# carte_ninja2026.net
KiCad netlist of a schematic drawn in Altium Designer
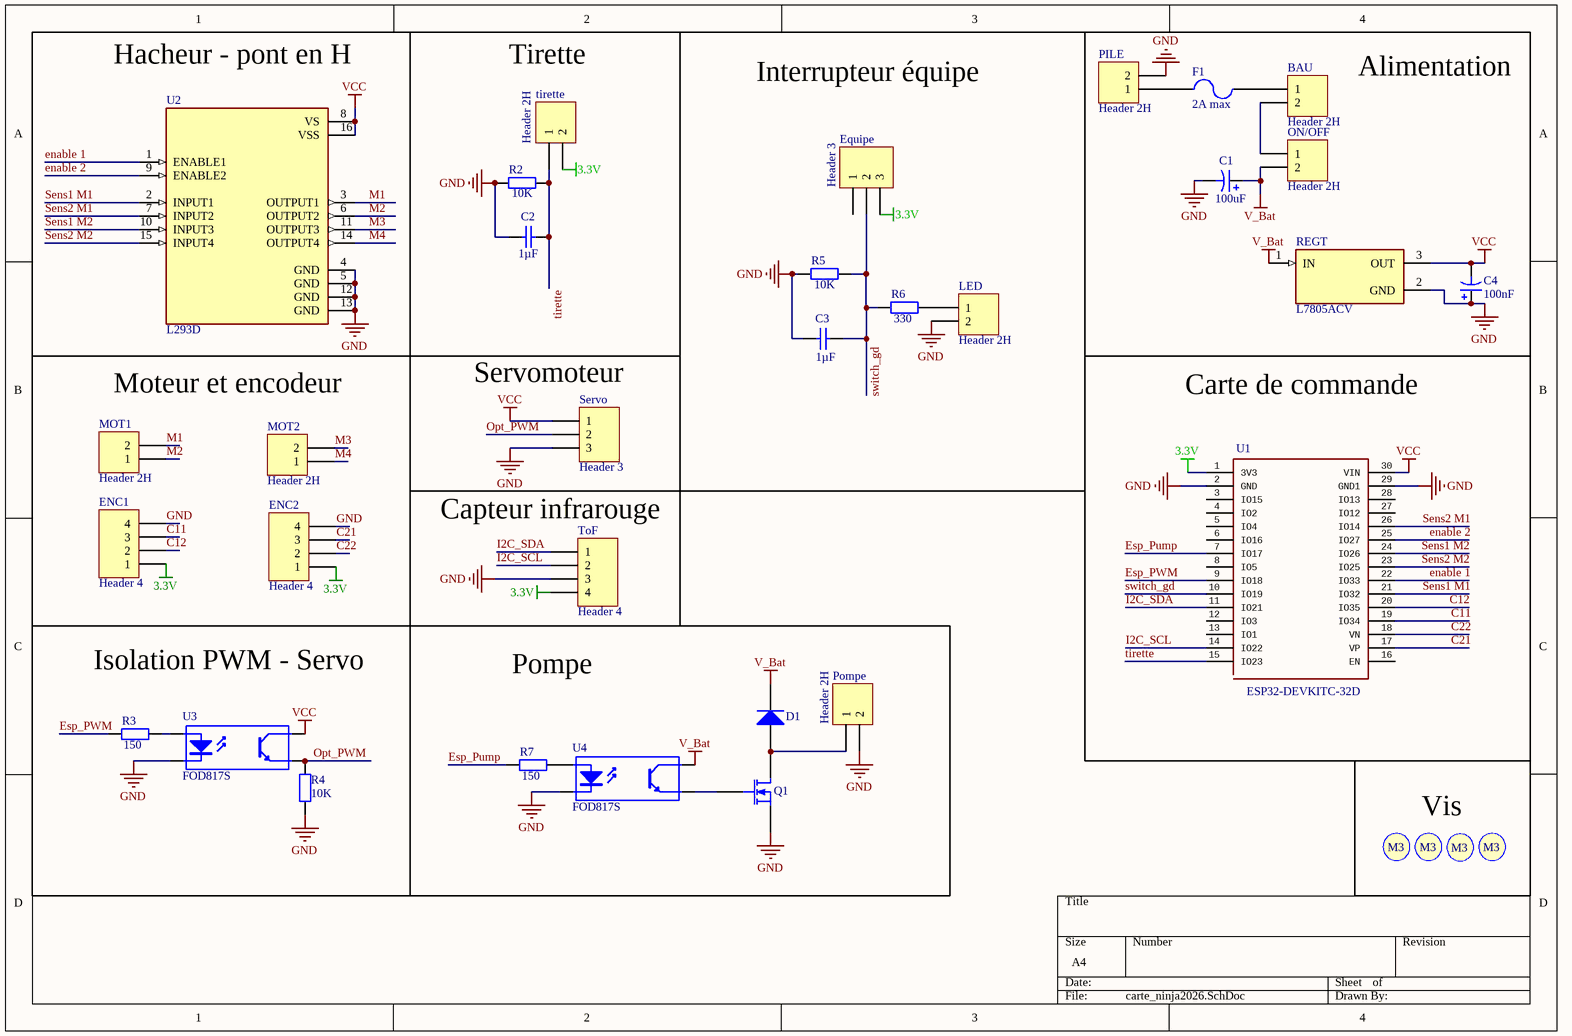
[diagram p0: carte_ninja2026.SchDoc]

(export (version "E")
  (design (tool "Eeschema 10.0.6"))
  (components
    (comp (ref "BAU")
      (value "Header 2H")
      (footprint "JST_B2B-XH-A_(LF)(SN)")
      (description "Header, 2-Pin, Right Angle")
      (fields (field (name "PUBLISHER") "Altium Limited"))
      (libsource (lib "") (part "Header 2H_1"))
    )
    (comp (ref "C1")
      (value "100uF")
      (footprint "Condensateur")
      (description "Polarized Capacitor (Radial)")
      (fields (field (name "Comment") "35V") (field (name "PUBLISHER") "Altium Limited"))
      (libsource (lib "Miscellaneous Devices") (part "Cap Pol1"))
    )
    (comp (ref "C2")
      (value "1µF")
      (footprint "Capacitor 1206")
      (description "Capacitor")
      (fields (field (name "Comment") "Cap") (field (name "PUBLISHER") "Altium Limited"))
      (libsource (lib "Miscellaneous Devices") (part "Cap"))
    )
    (comp (ref "C3")
      (value "1µF")
      (footprint "Capacitor 1206")
      (description "Capacitor")
      (fields (field (name "Comment") "Cap") (field (name "PUBLISHER") "Altium Limited"))
      (libsource (lib "Miscellaneous Devices") (part "Cap"))
    )
    (comp (ref "C4")
      (value "100nF")
      (footprint "Condensateur")
      (description "Polarized Capacitor (Radial)")
      (fields (field (name "Comment") "35V") (field (name "PUBLISHER") "Altium Limited"))
      (libsource (lib "Miscellaneous Devices") (part "Cap Pol1"))
    )
    (comp (ref "D1")
      (value "LGE SS12")
      (footprint "SMB")
      (description "Default Diode")
      (fields (field (name "PUBLISHER") "Altium Limited"))
      (libsource (lib "Miscellaneous Devices") (part "Diode"))
    )
    (comp (ref "ENC1")
      (value "Header 4")
      (footprint "B4BXHALFSN")
      (description "Header, 4-Pin")
      (fields (field (name "PUBLISHER") "Altium Limited"))
      (libsource (lib "Miscellaneous Connectors") (part "Header 4"))
    )
    (comp (ref "ENC2")
      (value "Header 4")
      (footprint "B4BXHALFSN")
      (description "Header, 4-Pin")
      (fields (field (name "PUBLISHER") "Altium Limited"))
      (libsource (lib "Miscellaneous Connectors") (part "Header 4"))
    )
    (comp (ref "Equipe")
      (value "Header 3")
      (footprint "JST_B3B-XH-A(LF)(SN)")
      (description "Header, 3-Pin")
      (fields (field (name "PUBLISHER") "Altium Limited"))
      (libsource (lib "") (part "Header 3_1"))
    )
    (comp (ref "F1")
      (value "2A max")
      (footprint "Fuse")
      (description "Main Fuse")
      (fields (field (name "PUBLISHER") "Altium Limited"))
      (libsource (lib "Miscellaneous Devices") (part "Fuse 2"))
    )
    (comp (ref "LED")
      (value "Header 2H")
      (footprint "JST_B2B-XH-A_(LF)(SN)")
      (description "Header, 2-Pin, Right Angle")
      (fields (field (name "PUBLISHER") "Altium Limited"))
      (libsource (lib "") (part "Header 2H_1"))
    )
    (comp (ref "MOT1")
      (value "Header 2H")
      (footprint "JST_B2B-XH-A_(LF)(SN)")
      (description "Header, 2-Pin, Right Angle")
      (fields (field (name "PUBLISHER") "Altium Limited"))
      (libsource (lib "Miscellaneous Connectors") (part "Header 2H"))
    )
    (comp (ref "MOT2")
      (value "Header 2H")
      (footprint "JST_B2B-XH-A_(LF)(SN)")
      (description "Header, 2-Pin, Right Angle")
      (fields (field (name "PUBLISHER") "Altium Limited"))
      (libsource (lib "Miscellaneous Connectors") (part "Header 2H"))
    )
    (comp (ref "ON/OFF")
      (value "Header 2H")
      (footprint "JST_B2B-XH-A_(LF)(SN)")
      (description "Header, 2-Pin, Right Angle")
      (fields (field (name "PUBLISHER") "Altium Limited"))
      (libsource (lib "") (part "Header 2H_1"))
    )
    (comp (ref "PILE")
      (value "Header 2H")
      (footprint "JST_B2B-XH-A_(LF)(SN)")
      (description "Header, 2-Pin, Right Angle")
      (fields (field (name "PUBLISHER") "Altium Limited"))
      (libsource (lib "Miscellaneous Connectors") (part "Header 2H"))
    )
    (comp (ref "Pompe")
      (value "Header 2H")
      (footprint "JST_B2B-XH-A_(LF)(SN)")
      (description "Header, 2-Pin, Right Angle")
      (fields (field (name "PUBLISHER") "Altium Limited"))
      (libsource (lib "") (part "Header 2H_2"))
    )
    (comp (ref "Q1")
      (value "MOSFET-N")
      (footprint "SOT23_M")
      (description "N-Channel MOSFET")
      (fields (field (name "PUBLISHER") "Altium Limited"))
      (libsource (lib "Miscellaneous Devices") (part "MOSFET-N"))
    )
    (comp (ref "R2")
      (value "10K")
      (footprint "Resistor 1206")
      (description "Resistor")
      (fields (field (name "Comment") "Res2") (field (name "PUBLISHER") "Altium Limited"))
      (libsource (lib "") (part "Res2_1"))
    )
    (comp (ref "R3")
      (value "150")
      (footprint "Resistor 1206")
      (description "Resistor")
      (fields (field (name "Comment") "Res2") (field (name "PUBLISHER") "Altium Limited"))
      (libsource (lib "") (part "Res2_1"))
    )
    (comp (ref "R4")
      (value "10K")
      (footprint "Resistor 1206")
      (description "Resistor")
      (fields (field (name "Comment") "Res2") (field (name "PUBLISHER") "Altium Limited"))
      (libsource (lib "Miscellaneous Devices") (part "Res2"))
    )
    (comp (ref "R5")
      (value "10K")
      (footprint "Resistor 1206")
      (description "Resistor")
      (fields (field (name "Comment") "Res2") (field (name "PUBLISHER") "Altium Limited"))
      (libsource (lib "") (part "Res2_1"))
    )
    (comp (ref "R6")
      (value "330")
      (footprint "Resistor 1206")
      (description "Resistor")
      (fields (field (name "Comment") "Res2") (field (name "PUBLISHER") "Altium Limited"))
      (libsource (lib "") (part "Res2_1"))
    )
    (comp (ref "R7")
      (value "150")
      (footprint "Resistor 1206")
      (description "Resistor")
      (fields (field (name "Comment") "Res2") (field (name "PUBLISHER") "Altium Limited"))
      (libsource (lib "") (part "Res2_1"))
    )
    (comp (ref "REGT")
      (value "L7805ACV")
      (footprint "TO254P460X1020X1945-3P")
      (description "Linear Voltage Regulator IC Positive Fixed 1 Output 1.5A TO-220")
      (fields (field (name "MF") "STMicroelectronics"))
      (libsource (lib "L7805ACV") (part "L7805ACV"))
    )
    (comp (ref "S0")
      (value "Screw M3")
      (footprint "Screw M3")
      (libsource (lib "Robot_2019") (part "Screw M3"))
    )
    (comp (ref "S1")
      (value "Screw M3")
      (footprint "Screw M3")
      (libsource (lib "Robot_2019") (part "Screw M3"))
    )
    (comp (ref "S2")
      (value "Screw M3")
      (footprint "Screw M3")
      (libsource (lib "Robot_2019") (part "Screw M3"))
    )
    (comp (ref "S3")
      (value "Screw M3")
      (footprint "Screw M3")
      (libsource (lib "Robot_2019") (part "Screw M3"))
    )
    (comp (ref "Servo")
      (value "Header 3")
      (footprint "JST_B3B-XH-A(LF)(SN)")
      (description "Header, 3-Pin")
      (fields (field (name "PUBLISHER") "Altium Limited"))
      (libsource (lib "Miscellaneous Connectors") (part "Header 3"))
    )
    (comp (ref "tirette")
      (value "Header 2H")
      (footprint "JST_B2B-XH-A_(LF)(SN)")
      (description "Header, 2-Pin, Right Angle")
      (fields (field (name "PUBLISHER") "Altium Limited"))
      (libsource (lib "") (part "Header 2H_2"))
    )
    (comp (ref "ToF")
      (value "Header 4")
      (footprint "B4BXHALFSN")
      (description "Header, 4-Pin")
      (fields (field (name "PUBLISHER") "Altium Limited"))
      (libsource (lib "") (part "Header 4_1"))
    )
    (comp (ref "U1")
      (value "ESP32-DEVKITC-32D")
      (footprint "MODULE_ESP32-DEVKITV1")
      (description "Eval Board For Esp-Wroom-32")
      (fields (field (name "MF") "Espressif Systems"))
      (libsource (lib "AltiumLibraryDDT") (part "ESP32-DEVKITC-32D"))
    )
    (comp (ref "U2")
      (value "L293D")
      (footprint "DIP880W50P254L2000H510Q16")
      (description "Bipolar Motor Driver - Parallel 16-PowerDIP")
      (fields (field (name "MF") "STMicroelectronics"))
      (libsource (lib "L293D") (part "L293D"))
    )
    (comp (ref "U3")
      (value "FOD817S")
      (footprint "SOP254P1016X385-4N")
      (description "4-Pin Phototransistor Optocoupler")
      (fields (field (name "PUBLISHER") "Altium Limited"))
      (libsource (lib "Miscellaneous Devices") (part "Optoisolator1"))
    )
    (comp (ref "U4")
      (value "FOD817S")
      (footprint "SOP254P1016X385-4N")
      (description "4-Pin Phototransistor Optocoupler")
      (fields (field (name "PUBLISHER") "Altium Limited"))
      (libsource (lib "Miscellaneous Devices") (part "Optoisolator1"))
    )
  )
  (nets
    (net (code "1") (name "/C11") (class "Default")
      (node (ref "ENC1") (pin "3") (pinfunction "3_3") (pintype "passive"))
      (node (ref "U1") (pin "19") (pinfunction "IO34_19") (pintype "passive"))
    )
    (net (code "2") (name "/C12") (class "Default")
      (node (ref "ENC1") (pin "2") (pinfunction "2_2") (pintype "passive"))
      (node (ref "U1") (pin "20") (pinfunction "IO35_20") (pintype "passive"))
    )
    (net (code "3") (name "/C21") (class "Default")
      (node (ref "ENC2") (pin "3") (pinfunction "3_3") (pintype "passive"))
      (node (ref "U1") (pin "17") (pinfunction "VP_17") (pintype "passive"))
    )
    (net (code "4") (name "/C22") (class "Default")
      (node (ref "ENC2") (pin "2") (pinfunction "2_2") (pintype "passive"))
      (node (ref "U1") (pin "18") (pinfunction "VN_18") (pintype "passive"))
    )
    (net (code "5") (name "/Esp_PWM") (class "Default")
      (node (ref "R3") (pin "1") (pinfunction "1_1") (pintype "passive"))
      (node (ref "U1") (pin "9") (pinfunction "IO18_9") (pintype "passive"))
    )
    (net (code "6") (name "/Esp_Pump") (class "Default")
      (node (ref "R7") (pin "1") (pinfunction "1_1") (pintype "passive"))
      (node (ref "U1") (pin "7") (pinfunction "IO17_7") (pintype "passive"))
    )
    (net (code "7") (name "/I2C_SCL") (class "Default")
      (node (ref "ToF") (pin "2") (pinfunction "2_2") (pintype "passive"))
      (node (ref "U1") (pin "14") (pinfunction "IO22_14") (pintype "passive"))
    )
    (net (code "8") (name "/I2C_SDA") (class "Default")
      (node (ref "ToF") (pin "1") (pinfunction "1_1") (pintype "passive"))
      (node (ref "U1") (pin "11") (pinfunction "IO21_11") (pintype "passive"))
    )
    (net (code "9") (name "/M1") (class "Default")
      (node (ref "MOT1") (pin "2") (pinfunction "2_2") (pintype "passive"))
      (node (ref "U2") (pin "3") (pinfunction "OUTPUT1_3") (pintype "output"))
    )
    (net (code "10") (name "/M2") (class "Default")
      (node (ref "MOT1") (pin "1") (pinfunction "1_1") (pintype "passive"))
      (node (ref "U2") (pin "6") (pinfunction "OUTPUT2_6") (pintype "output"))
    )
    (net (code "11") (name "/M3") (class "Default")
      (node (ref "MOT2") (pin "2") (pinfunction "2_2") (pintype "passive"))
      (node (ref "U2") (pin "11") (pinfunction "OUTPUT3_11") (pintype "output"))
    )
    (net (code "12") (name "/M4") (class "Default")
      (node (ref "MOT2") (pin "1") (pinfunction "1_1") (pintype "passive"))
      (node (ref "U2") (pin "14") (pinfunction "OUTPUT4_14") (pintype "output"))
    )
    (net (code "13") (name "/Opt_PWM") (class "Default")
      (node (ref "R4") (pin "2") (pinfunction "2_2") (pintype "passive"))
      (node (ref "Servo") (pin "2") (pinfunction "2_2") (pintype "passive"))
      (node (ref "U3") (pin "3") (pinfunction "E_3") (pintype "passive"))
    )
    (net (code "14") (name "/Sens1 M1") (class "Default")
      (node (ref "U1") (pin "21") (pinfunction "IO32_21") (pintype "passive"))
      (node (ref "U2") (pin "2") (pinfunction "INPUT1_2") (pintype "input"))
    )
    (net (code "15") (name "/Sens1 M2") (class "Default")
      (node (ref "U1") (pin "24") (pinfunction "IO26_24") (pintype "passive"))
      (node (ref "U2") (pin "10") (pinfunction "INPUT3_10") (pintype "input"))
    )
    (net (code "16") (name "/Sens2 M1") (class "Default")
      (node (ref "U1") (pin "26") (pinfunction "IO14_26") (pintype "passive"))
      (node (ref "U2") (pin "7") (pinfunction "INPUT2_7") (pintype "input"))
    )
    (net (code "17") (name "/Sens2 M2") (class "Default")
      (node (ref "U1") (pin "23") (pinfunction "IO25_23") (pintype "passive"))
      (node (ref "U2") (pin "15") (pinfunction "INPUT4_15") (pintype "input"))
    )
    (net (code "18") (name "/enable 1") (class "Default")
      (node (ref "U1") (pin "22") (pinfunction "IO33_22") (pintype "passive"))
      (node (ref "U2") (pin "1") (pinfunction "ENABLE1_1") (pintype "input"))
    )
    (net (code "19") (name "/enable 2") (class "Default")
      (node (ref "U1") (pin "25") (pinfunction "IO27_25") (pintype "passive"))
      (node (ref "U2") (pin "9") (pinfunction "ENABLE2_9") (pintype "input"))
    )
    (net (code "20") (name "/switch_gd") (class "Default")
      (node (ref "C3") (pin "2") (pinfunction "2_2") (pintype "passive"))
      (node (ref "Equipe") (pin "2") (pinfunction "2_2") (pintype "passive"))
      (node (ref "R5") (pin "2") (pinfunction "2_2") (pintype "passive"))
      (node (ref "R6") (pin "1") (pinfunction "1_1") (pintype "passive"))
      (node (ref "U1") (pin "10") (pinfunction "IO19_10") (pintype "passive"))
    )
    (net (code "21") (name "/tirette") (class "Default")
      (node (ref "C2") (pin "2") (pinfunction "2_2") (pintype "passive"))
      (node (ref "R2") (pin "2") (pinfunction "2_2") (pintype "passive"))
      (node (ref "U1") (pin "15") (pinfunction "IO23_15") (pintype "passive"))
      (node (ref "tirette") (pin "1") (pinfunction "1_1") (pintype "passive"))
    )
    (net (code "22") (name "3.3V") (class "Default")
      (node (ref "ENC1") (pin "1") (pinfunction "1_1") (pintype "passive"))
      (node (ref "ENC2") (pin "1") (pinfunction "1_1") (pintype "passive"))
      (node (ref "Equipe") (pin "3") (pinfunction "3_3") (pintype "passive"))
      (node (ref "ToF") (pin "4") (pinfunction "4_4") (pintype "passive"))
      (node (ref "U1") (pin "1") (pinfunction "3V3_1") (pintype "passive"))
      (node (ref "tirette") (pin "2") (pinfunction "2_2") (pintype "passive"))
    )
    (net (code "23") (name "GND") (class "Default")
      (node (ref "C1") (pin "2") (pinfunction "2_2") (pintype "passive"))
      (node (ref "C2") (pin "1") (pinfunction "1_1") (pintype "passive"))
      (node (ref "C3") (pin "1") (pinfunction "1_1") (pintype "passive"))
      (node (ref "C4") (pin "1") (pinfunction "1_1") (pintype "passive"))
      (node (ref "ENC1") (pin "4") (pinfunction "4_4") (pintype "passive"))
      (node (ref "ENC2") (pin "4") (pinfunction "4_4") (pintype "passive"))
      (node (ref "LED") (pin "2") (pinfunction "2_2") (pintype "passive"))
      (node (ref "PILE") (pin "2") (pinfunction "2_2") (pintype "passive"))
      (node (ref "Pompe") (pin "2") (pinfunction "2_2") (pintype "passive"))
      (node (ref "Q1") (pin "3") (pinfunction "S_3") (pintype "passive"))
      (node (ref "R2") (pin "1") (pinfunction "1_1") (pintype "passive"))
      (node (ref "R4") (pin "1") (pinfunction "1_1") (pintype "passive"))
      (node (ref "R5") (pin "1") (pinfunction "1_1") (pintype "passive"))
      (node (ref "REGT") (pin "2") (pinfunction "GND_2") (pintype "power_in"))
      (node (ref "Servo") (pin "3") (pinfunction "3_3") (pintype "passive"))
      (node (ref "ToF") (pin "3") (pinfunction "3_3") (pintype "passive"))
      (node (ref "U1") (pin "2") (pinfunction "GND_2") (pintype "passive"))
      (node (ref "U1") (pin "29") (pinfunction "GND1_29") (pintype "passive"))
      (node (ref "U2") (pin "12") (pinfunction "GND_12") (pintype "power_in"))
      (node (ref "U2") (pin "13") (pinfunction "GND_13") (pintype "power_in"))
      (node (ref "U2") (pin "4") (pinfunction "GND_4") (pintype "power_in"))
      (node (ref "U2") (pin "5") (pinfunction "GND_5") (pintype "power_in"))
      (node (ref "U3") (pin "2") (pinfunction "K_2") (pintype "passive"))
      (node (ref "U4") (pin "2") (pinfunction "K_2") (pintype "passive"))
    )
    (net (code "24") (name "Net-(BAU-Pad1)") (class "Default")
      (node (ref "BAU") (pin "1") (pinfunction "1_1") (pintype "passive"))
      (node (ref "F1") (pin "1") (pinfunction "1_1") (pintype "passive"))
    )
    (net (code "25") (name "Net-(BAU-Pad2)") (class "Default")
      (node (ref "BAU") (pin "2") (pinfunction "2_2") (pintype "passive"))
      (node (ref "ON/OFF") (pin "1") (pinfunction "1_1") (pintype "passive"))
    )
    (net (code "26") (name "Net-(D1-A)") (class "Default")
      (node (ref "D1") (pin "1") (pinfunction "A_1") (pintype "passive"))
      (node (ref "Pompe") (pin "1") (pinfunction "1_1") (pintype "passive"))
      (node (ref "Q1") (pin "1") (pinfunction "D_1") (pintype "passive"))
    )
    (net (code "27") (name "Net-(F1-Pad2)") (class "Default")
      (node (ref "F1") (pin "2") (pinfunction "2_2") (pintype "passive"))
      (node (ref "PILE") (pin "1") (pinfunction "1_1") (pintype "passive"))
    )
    (net (code "28") (name "Net-(LED-Pad1)") (class "Default")
      (node (ref "LED") (pin "1") (pinfunction "1_1") (pintype "passive"))
      (node (ref "R6") (pin "2") (pinfunction "2_2") (pintype "passive"))
    )
    (net (code "29") (name "Net-(Q1-G)") (class "Default")
      (node (ref "Q1") (pin "2") (pinfunction "G_2") (pintype "passive"))
      (node (ref "U4") (pin "3") (pinfunction "E_3") (pintype "passive"))
    )
    (net (code "30") (name "Net-(U3-A)") (class "Default")
      (node (ref "R3") (pin "2") (pinfunction "2_2") (pintype "passive"))
      (node (ref "U3") (pin "1") (pinfunction "A_1") (pintype "passive"))
    )
    (net (code "31") (name "Net-(U4-A)") (class "Default")
      (node (ref "R7") (pin "2") (pinfunction "2_2") (pintype "passive"))
      (node (ref "U4") (pin "1") (pinfunction "A_1") (pintype "passive"))
    )
    (net (code "32") (name "VCC") (class "Default")
      (node (ref "C4") (pin "2") (pinfunction "2_2") (pintype "passive"))
      (node (ref "REGT") (pin "3") (pinfunction "OUT_3") (pintype "power_in"))
      (node (ref "Servo") (pin "1") (pinfunction "1_1") (pintype "passive"))
      (node (ref "U1") (pin "30") (pinfunction "VIN_30") (pintype "passive"))
      (node (ref "U2") (pin "16") (pinfunction "VSS_16") (pintype "power_in"))
      (node (ref "U2") (pin "8") (pinfunction "VS_8") (pintype "power_in"))
      (node (ref "U3") (pin "4") (pinfunction "C_4") (pintype "passive"))
    )
    (net (code "33") (name "V_Bat") (class "Default")
      (node (ref "C1") (pin "1") (pinfunction "1_1") (pintype "passive"))
      (node (ref "D1") (pin "2") (pinfunction "K_2") (pintype "passive"))
      (node (ref "ON/OFF") (pin "2") (pinfunction "2_2") (pintype "passive"))
      (node (ref "REGT") (pin "1") (pinfunction "IN_1") (pintype "input"))
      (node (ref "U4") (pin "4") (pinfunction "C_4") (pintype "passive"))
    )
    (net (code "34") (name "unconnected-(Equipe-Pad1)") (class "Default")
      (node (ref "Equipe") (pin "1") (pinfunction "1_1") (pintype "passive"))
    )
    (net (code "35") (name "unconnected-(U1-EN-Pad16)") (class "Default")
      (node (ref "U1") (pin "16") (pinfunction "EN_16") (pintype "passive"))
    )
    (net (code "36") (name "unconnected-(U1-IO1-Pad13)") (class "Default")
      (node (ref "U1") (pin "13") (pinfunction "IO1_13") (pintype "passive"))
    )
    (net (code "37") (name "unconnected-(U1-IO2-Pad4)") (class "Default")
      (node (ref "U1") (pin "4") (pinfunction "IO2_4") (pintype "passive"))
    )
    (net (code "38") (name "unconnected-(U1-IO3-Pad12)") (class "Default")
      (node (ref "U1") (pin "12") (pinfunction "IO3_12") (pintype "passive"))
    )
    (net (code "39") (name "unconnected-(U1-IO4-Pad5)") (class "Default")
      (node (ref "U1") (pin "5") (pinfunction "IO4_5") (pintype "passive"))
    )
    (net (code "40") (name "unconnected-(U1-IO5-Pad8)") (class "Default")
      (node (ref "U1") (pin "8") (pinfunction "IO5_8") (pintype "passive"))
    )
    (net (code "41") (name "unconnected-(U1-IO12-Pad27)") (class "Default")
      (node (ref "U1") (pin "27") (pinfunction "IO12_27") (pintype "passive"))
    )
    (net (code "42") (name "unconnected-(U1-IO13-Pad28)") (class "Default")
      (node (ref "U1") (pin "28") (pinfunction "IO13_28") (pintype "passive"))
    )
    (net (code "43") (name "unconnected-(U1-IO15-Pad3)") (class "Default")
      (node (ref "U1") (pin "3") (pinfunction "IO15_3") (pintype "passive"))
    )
    (net (code "44") (name "unconnected-(U1-IO16-Pad6)") (class "Default")
      (node (ref "U1") (pin "6") (pinfunction "IO16_6") (pintype "passive"))
    )
  )
)
